# offset_rectifier.net
KiCad netlist of a schematic drawn in EAGLE
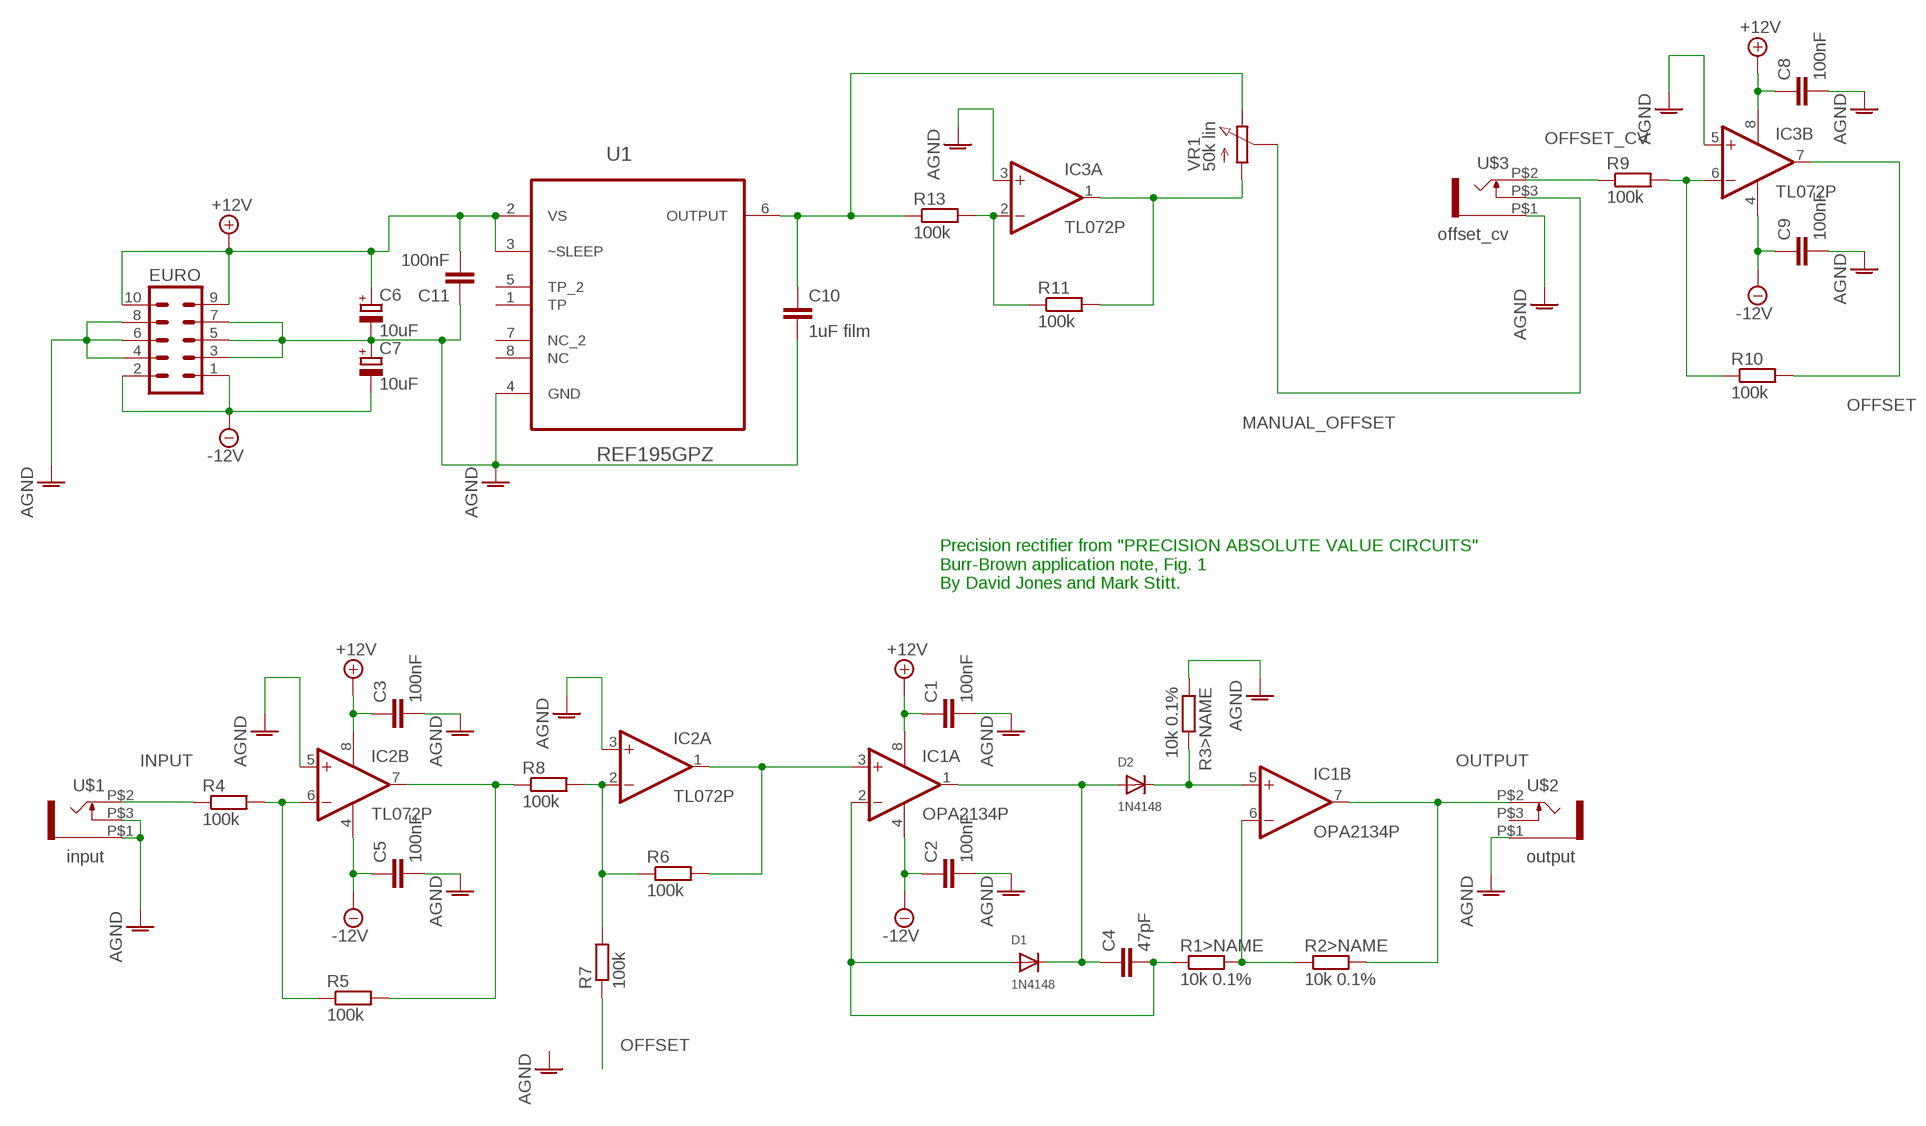
[diagram p0: schematic, sheet 1]

(export (version "E")
  (design (tool "Eeschema 10.0.6"))
  (components
    (comp (ref "C1")
      (value "100nF")
      (footprint "eagle-import:C2.5-3")
      (libsource (lib "eagle-import") (part "C2,5-3"))
    )
    (comp (ref "C2")
      (value "100nF")
      (footprint "eagle-import:C2.5-3")
      (libsource (lib "eagle-import") (part "C2,5-3"))
    )
    (comp (ref "C3")
      (value "100nF")
      (footprint "eagle-import:C2.5-3")
      (libsource (lib "eagle-import") (part "C2,5-3"))
    )
    (comp (ref "C4")
      (value "47pF")
      (footprint "eagle-import:C2.5-3")
      (libsource (lib "eagle-import") (part "C2,5-3"))
    )
    (comp (ref "C5")
      (value "100nF")
      (footprint "eagle-import:C2.5-3")
      (libsource (lib "eagle-import") (part "C2,5-3"))
    )
    (comp (ref "C6")
      (value "10uF")
      (footprint "eagle-import:E2,5-6E")
      (libsource (lib "eagle-import") (part "CPOL-EUE2,5-6E"))
    )
    (comp (ref "C7")
      (value "10uF")
      (footprint "eagle-import:E2,5-6E")
      (libsource (lib "eagle-import") (part "CPOL-EUE2,5-6E"))
    )
    (comp (ref "C8")
      (value "100nF")
      (footprint "eagle-import:C2.5-3")
      (libsource (lib "eagle-import") (part "C2,5-3"))
    )
    (comp (ref "C9")
      (value "100nF")
      (footprint "eagle-import:C2.5-3")
      (libsource (lib "eagle-import") (part "C2,5-3"))
    )
    (comp (ref "C10")
      (value "1uF film")
      (footprint "eagle-import:C050-025X075")
      (libsource (lib "eagle-import") (part "C-EU050-025X075"))
    )
    (comp (ref "C11")
      (value "100nF")
      (footprint "eagle-import:C2.5-3")
      (libsource (lib "eagle-import") (part "C2,5-3"))
    )
    (comp (ref "D1")
      (value "1N4148")
      (footprint "eagle-import:DO-1N4148")
      (libsource (lib "eagle-import") (part "DIODEDO-1N4148"))
    )
    (comp (ref "D2")
      (value "1N4148")
      (footprint "eagle-import:DO-1N4148")
      (libsource (lib "eagle-import") (part "DIODEDO-1N4148"))
    )
    (comp (ref "EURO")
      (value "MA05-2")
      (footprint "eagle-import:MA05-2")
      (libsource (lib "eagle-import") (part "MA05-2"))
    )
    (comp (ref "IC1")
      (value "OPA2134P")
      (footprint "eagle-import:DIL08")
      (libsource (lib "eagle-import") (part "OPA2134P"))
    )
    (comp (ref "IC2")
      (value "TL072P")
      (footprint "eagle-import:DIL08")
      (libsource (lib "eagle-import") (part "TL072P"))
    )
    (comp (ref "IC3")
      (value "TL072P")
      (footprint "eagle-import:DIL08")
      (libsource (lib "eagle-import") (part "TL072P"))
    )
    (comp (ref "R1")
      (value "10k 0.1%")
      (footprint "eagle-import:0409_12.5")
      (libsource (lib "eagle-import") (part "WELWYN_PR5"))
    )
    (comp (ref "R2")
      (value "10k 0.1%")
      (footprint "eagle-import:0409_12.5")
      (libsource (lib "eagle-import") (part "WELWYN_PR5"))
    )
    (comp (ref "R3")
      (value "10k 0.1%")
      (footprint "eagle-import:0409_12.5")
      (libsource (lib "eagle-import") (part "WELWYN_PR5"))
    )
    (comp (ref "R4")
      (value "100k")
      (footprint "eagle-import:02.5-06.8_10")
      (libsource (lib "eagle-import") (part "MULTICOMP_MF25"))
    )
    (comp (ref "R5")
      (value "100k")
      (footprint "eagle-import:02.5-06.8_10")
      (libsource (lib "eagle-import") (part "MULTICOMP_MF25"))
    )
    (comp (ref "R6")
      (value "100k")
      (footprint "eagle-import:02.5-06.8_10")
      (libsource (lib "eagle-import") (part "MULTICOMP_MF25"))
    )
    (comp (ref "R7")
      (value "100k")
      (footprint "eagle-import:02.5-06.8_10")
      (libsource (lib "eagle-import") (part "MULTICOMP_MF25"))
    )
    (comp (ref "R8")
      (value "100k")
      (footprint "eagle-import:02.5-06.8_10")
      (libsource (lib "eagle-import") (part "MULTICOMP_MF25"))
    )
    (comp (ref "R9")
      (value "100k")
      (footprint "eagle-import:02.5-06.8_10")
      (libsource (lib "eagle-import") (part "MULTICOMP_MF25"))
    )
    (comp (ref "R10")
      (value "100k")
      (footprint "eagle-import:02.5-06.8_10")
      (libsource (lib "eagle-import") (part "MULTICOMP_MF25"))
    )
    (comp (ref "R11")
      (value "100k")
      (footprint "eagle-import:02.5-06.8_10")
      (libsource (lib "eagle-import") (part "MULTICOMP_MF25"))
    )
    (comp (ref "R13")
      (value "100k")
      (footprint "eagle-import:02.5-06.8_10")
      (libsource (lib "eagle-import") (part "MULTICOMP_MF25"))
    )
    (comp (ref "U$1")
      (value "input")
      (footprint "eagle-import:PJ302M")
      (libsource (lib "eagle-import") (part "PJ302M-ROUND"))
    )
    (comp (ref "U$2")
      (value "output")
      (footprint "eagle-import:PJ302M")
      (libsource (lib "eagle-import") (part "PJ302M-ROUND"))
    )
    (comp (ref "U$3")
      (value "offset_cv")
      (footprint "eagle-import:PJ302M")
      (libsource (lib "eagle-import") (part "PJ302M-ROUND"))
    )
    (comp (ref "U1")
      (value "REF195GPZ")
      (footprint "eagle-import:DIP254P762X533-8")
      (libsource (lib "eagle-import") (part "REF195GPZ"))
    )
    (comp (ref "VR1")
      (value "50k lin")
      (footprint "eagle-import:BI_9MM_SIDE")
      (libsource (lib "eagle-import") (part "BI_P09X"))
    )
  )
  (nets
    (net (code "1") (name "+12V") (class "Default")
      (node (ref "C1") (pin "1") (pinfunction "1_1") (pintype "passive"))
      (node (ref "C11") (pin "2") (pinfunction "2_2") (pintype "passive"))
      (node (ref "C3") (pin "1") (pinfunction "1_1") (pintype "passive"))
      (node (ref "C6") (pin "+") (pinfunction "+_+") (pintype "passive"))
      (node (ref "C8") (pin "1") (pinfunction "1_1") (pintype "passive"))
      (node (ref "EURO") (pin "10") (pinfunction "10_10") (pintype "passive"))
      (node (ref "EURO") (pin "9") (pinfunction "9_9") (pintype "passive"))
      (node (ref "IC1") (pin "8") (pinfunction "V+_8") (pintype "power_in"))
      (node (ref "IC2") (pin "8") (pinfunction "V+_8") (pintype "power_in"))
      (node (ref "IC3") (pin "8") (pinfunction "V+_8") (pintype "power_in"))
      (node (ref "U1") (pin "2") (pinfunction "VS_2") (pintype "power_in"))
      (node (ref "U1") (pin "3") (pinfunction "~{SLEEP}_3") (pintype "input"))
    )
    (net (code "2") (name "-12V") (class "Default")
      (node (ref "C2") (pin "1") (pinfunction "1_1") (pintype "passive"))
      (node (ref "C5") (pin "1") (pinfunction "1_1") (pintype "passive"))
      (node (ref "C7") (pin "-") (pinfunction "-_-") (pintype "passive"))
      (node (ref "C9") (pin "1") (pinfunction "1_1") (pintype "passive"))
      (node (ref "EURO") (pin "1") (pinfunction "1_1") (pintype "passive"))
      (node (ref "EURO") (pin "2") (pinfunction "2_2") (pintype "passive"))
      (node (ref "IC1") (pin "4") (pinfunction "V-_4") (pintype "power_in"))
      (node (ref "IC2") (pin "4") (pinfunction "V-_4") (pintype "power_in"))
      (node (ref "IC3") (pin "4") (pinfunction "V-_4") (pintype "power_in"))
    )
    (net (code "3") (name "/INPUT") (class "Default")
      (node (ref "R4") (pin "P$1") (pinfunction "1_P$1") (pintype "passive"))
      (node (ref "U$1") (pin "P$2") (pinfunction "TIP_P$2") (pintype "passive"))
    )
    (net (code "4") (name "/MANUAL_OFFSET") (class "Default")
      (node (ref "U$3") (pin "P$3") (pinfunction "SWITCH_P$3") (pintype "passive"))
      (node (ref "VR1") (pin "WIPER") (pinfunction "WIPER_WIPER") (pintype "passive"))
    )
    (net (code "5") (name "/OFFSET") (class "Default")
      (node (ref "IC3") (pin "7") (pinfunction "OUT_7") (pintype "output"))
      (node (ref "R10") (pin "P$2") (pinfunction "2_P$2") (pintype "passive"))
      (node (ref "R7") (pin "P$1") (pinfunction "1_P$1") (pintype "passive"))
    )
    (net (code "6") (name "/OFFSET_CV") (class "Default")
      (node (ref "R9") (pin "P$1") (pinfunction "1_P$1") (pintype "passive"))
      (node (ref "U$3") (pin "P$2") (pinfunction "TIP_P$2") (pintype "passive"))
    )
    (net (code "7") (name "/OUTPUT") (class "Default")
      (node (ref "IC1") (pin "7") (pinfunction "OUT_7") (pintype "output"))
      (node (ref "R2") (pin "P$2") (pinfunction "2_P$2") (pintype "passive"))
      (node (ref "U$2") (pin "P$2") (pinfunction "TIP_P$2") (pintype "passive"))
    )
    (net (code "8") (name "AGND") (class "Default")
      (node (ref "C1") (pin "2") (pinfunction "2_2") (pintype "passive"))
      (node (ref "C10") (pin "2") (pinfunction "2_2") (pintype "passive"))
      (node (ref "C11") (pin "1") (pinfunction "1_1") (pintype "passive"))
      (node (ref "C2") (pin "2") (pinfunction "2_2") (pintype "passive"))
      (node (ref "C3") (pin "2") (pinfunction "2_2") (pintype "passive"))
      (node (ref "C5") (pin "2") (pinfunction "2_2") (pintype "passive"))
      (node (ref "C6") (pin "-") (pinfunction "-_-") (pintype "passive"))
      (node (ref "C7") (pin "+") (pinfunction "+_+") (pintype "passive"))
      (node (ref "C8") (pin "2") (pinfunction "2_2") (pintype "passive"))
      (node (ref "C9") (pin "2") (pinfunction "2_2") (pintype "passive"))
      (node (ref "EURO") (pin "3") (pinfunction "3_3") (pintype "passive"))
      (node (ref "EURO") (pin "4") (pinfunction "4_4") (pintype "passive"))
      (node (ref "EURO") (pin "5") (pinfunction "5_5") (pintype "passive"))
      (node (ref "EURO") (pin "6") (pinfunction "6_6") (pintype "passive"))
      (node (ref "EURO") (pin "7") (pinfunction "7_7") (pintype "passive"))
      (node (ref "EURO") (pin "8") (pinfunction "8_8") (pintype "passive"))
      (node (ref "IC2") (pin "3") (pinfunction "+IN_3") (pintype "input"))
      (node (ref "IC2") (pin "5") (pinfunction "+IN_5") (pintype "input"))
      (node (ref "IC3") (pin "3") (pinfunction "+IN_3") (pintype "input"))
      (node (ref "IC3") (pin "5") (pinfunction "+IN_5") (pintype "input"))
      (node (ref "R3") (pin "R$1") (pinfunction "1_R$1") (pintype "passive"))
      (node (ref "U$1") (pin "P$1") (pinfunction "RING_P$1") (pintype "passive"))
      (node (ref "U$1") (pin "P$3") (pinfunction "SWITCH_P$3") (pintype "passive"))
      (node (ref "U$2") (pin "P$1") (pinfunction "RING_P$1") (pintype "passive"))
      (node (ref "U$3") (pin "P$1") (pinfunction "RING_P$1") (pintype "passive"))
      (node (ref "U1") (pin "4") (pinfunction "GND_4") (pintype "passive"))
    )
    (net (code "9") (name "Net-(IC1A-+IN)") (class "Default")
      (node (ref "IC1") (pin "3") (pinfunction "+IN_3") (pintype "input"))
      (node (ref "IC2") (pin "1") (pinfunction "OUT_1") (pintype "output"))
      (node (ref "R6") (pin "P$2") (pinfunction "2_P$2") (pintype "passive"))
    )
    (net (code "10") (name "Net-(IC1A--IN)") (class "Default")
      (node (ref "C4") (pin "2") (pinfunction "2_2") (pintype "passive"))
      (node (ref "D1") (pin "A") (pinfunction "A_A") (pintype "passive"))
      (node (ref "IC1") (pin "2") (pinfunction "-IN_2") (pintype "input"))
      (node (ref "R1") (pin "R$1") (pinfunction "1_R$1") (pintype "passive"))
    )
    (net (code "11") (name "Net-(IC1A-OUT)") (class "Default")
      (node (ref "C4") (pin "1") (pinfunction "1_1") (pintype "passive"))
      (node (ref "D1") (pin "C") (pinfunction "C_C") (pintype "passive"))
      (node (ref "D2") (pin "A") (pinfunction "A_A") (pintype "passive"))
      (node (ref "IC1") (pin "1") (pinfunction "OUT_1") (pintype "output"))
    )
    (net (code "12") (name "Net-(IC1B-+IN)") (class "Default")
      (node (ref "D2") (pin "C") (pinfunction "C_C") (pintype "passive"))
      (node (ref "IC1") (pin "5") (pinfunction "+IN_5") (pintype "input"))
      (node (ref "R3") (pin "P$2") (pinfunction "2_P$2") (pintype "passive"))
    )
    (net (code "13") (name "Net-(IC1B--IN)") (class "Default")
      (node (ref "IC1") (pin "6") (pinfunction "-IN_6") (pintype "input"))
      (node (ref "R1") (pin "P$2") (pinfunction "2_P$2") (pintype "passive"))
      (node (ref "R2") (pin "R$1") (pinfunction "1_R$1") (pintype "passive"))
    )
    (net (code "14") (name "Net-(IC2A--IN)") (class "Default")
      (node (ref "IC2") (pin "2") (pinfunction "-IN_2") (pintype "input"))
      (node (ref "R6") (pin "P$1") (pinfunction "1_P$1") (pintype "passive"))
      (node (ref "R7") (pin "P$2") (pinfunction "2_P$2") (pintype "passive"))
      (node (ref "R8") (pin "P$2") (pinfunction "2_P$2") (pintype "passive"))
    )
    (net (code "15") (name "Net-(IC2B--IN)") (class "Default")
      (node (ref "IC2") (pin "6") (pinfunction "-IN_6") (pintype "input"))
      (node (ref "R4") (pin "P$2") (pinfunction "2_P$2") (pintype "passive"))
      (node (ref "R5") (pin "P$1") (pinfunction "1_P$1") (pintype "passive"))
    )
    (net (code "16") (name "Net-(IC2B-OUT)") (class "Default")
      (node (ref "IC2") (pin "7") (pinfunction "OUT_7") (pintype "output"))
      (node (ref "R5") (pin "P$2") (pinfunction "2_P$2") (pintype "passive"))
      (node (ref "R8") (pin "P$1") (pinfunction "1_P$1") (pintype "passive"))
    )
    (net (code "17") (name "Net-(IC3A--IN)") (class "Default")
      (node (ref "IC3") (pin "2") (pinfunction "-IN_2") (pintype "input"))
      (node (ref "R11") (pin "P$1") (pinfunction "1_P$1") (pintype "passive"))
      (node (ref "R13") (pin "P$2") (pinfunction "2_P$2") (pintype "passive"))
    )
    (net (code "18") (name "Net-(IC3A-OUT)") (class "Default")
      (node (ref "IC3") (pin "1") (pinfunction "OUT_1") (pintype "output"))
      (node (ref "R11") (pin "P$2") (pinfunction "2_P$2") (pintype "passive"))
      (node (ref "VR1") (pin "BOTTOM") (pinfunction "BOTTOM_BOTTOM") (pintype "passive"))
    )
    (net (code "19") (name "Net-(IC3B--IN)") (class "Default")
      (node (ref "IC3") (pin "6") (pinfunction "-IN_6") (pintype "input"))
      (node (ref "R10") (pin "P$1") (pinfunction "1_P$1") (pintype "passive"))
      (node (ref "R9") (pin "P$2") (pinfunction "2_P$2") (pintype "passive"))
    )
    (net (code "20") (name "Net-(R13-1)") (class "Default")
      (node (ref "C10") (pin "1") (pinfunction "1_1") (pintype "passive"))
      (node (ref "R13") (pin "P$1") (pinfunction "1_P$1") (pintype "passive"))
      (node (ref "U1") (pin "6") (pinfunction "OUTPUT_6") (pintype "output"))
      (node (ref "VR1") (pin "TOP") (pinfunction "TOP_TOP") (pintype "passive"))
    )
    (net (code "21") (name "unconnected-(U$2-SWITCH-PadP$3)") (class "Default")
      (node (ref "U$2") (pin "P$3") (pinfunction "SWITCH_P$3") (pintype "passive"))
    )
    (net (code "22") (name "unconnected-(U1-NC-Pad8)") (class "Default")
      (node (ref "U1") (pin "8") (pinfunction "NC_8") (pintype "no_connect"))
    )
    (net (code "23") (name "unconnected-(U1-NC_2-Pad7)") (class "Default")
      (node (ref "U1") (pin "7") (pinfunction "NC_2_7") (pintype "no_connect"))
    )
    (net (code "24") (name "unconnected-(U1-TP-Pad1)") (class "Default")
      (node (ref "U1") (pin "1") (pinfunction "TP_1") (pintype "passive"))
    )
    (net (code "25") (name "unconnected-(U1-TP_2-Pad5)") (class "Default")
      (node (ref "U1") (pin "5") (pinfunction "TP_2_5") (pintype "passive"))
    )
  )
)
